# Esp32_Wroom_Contr_le_de_DELs.net
KiCad netlist of a schematic drawn in Altium Designer
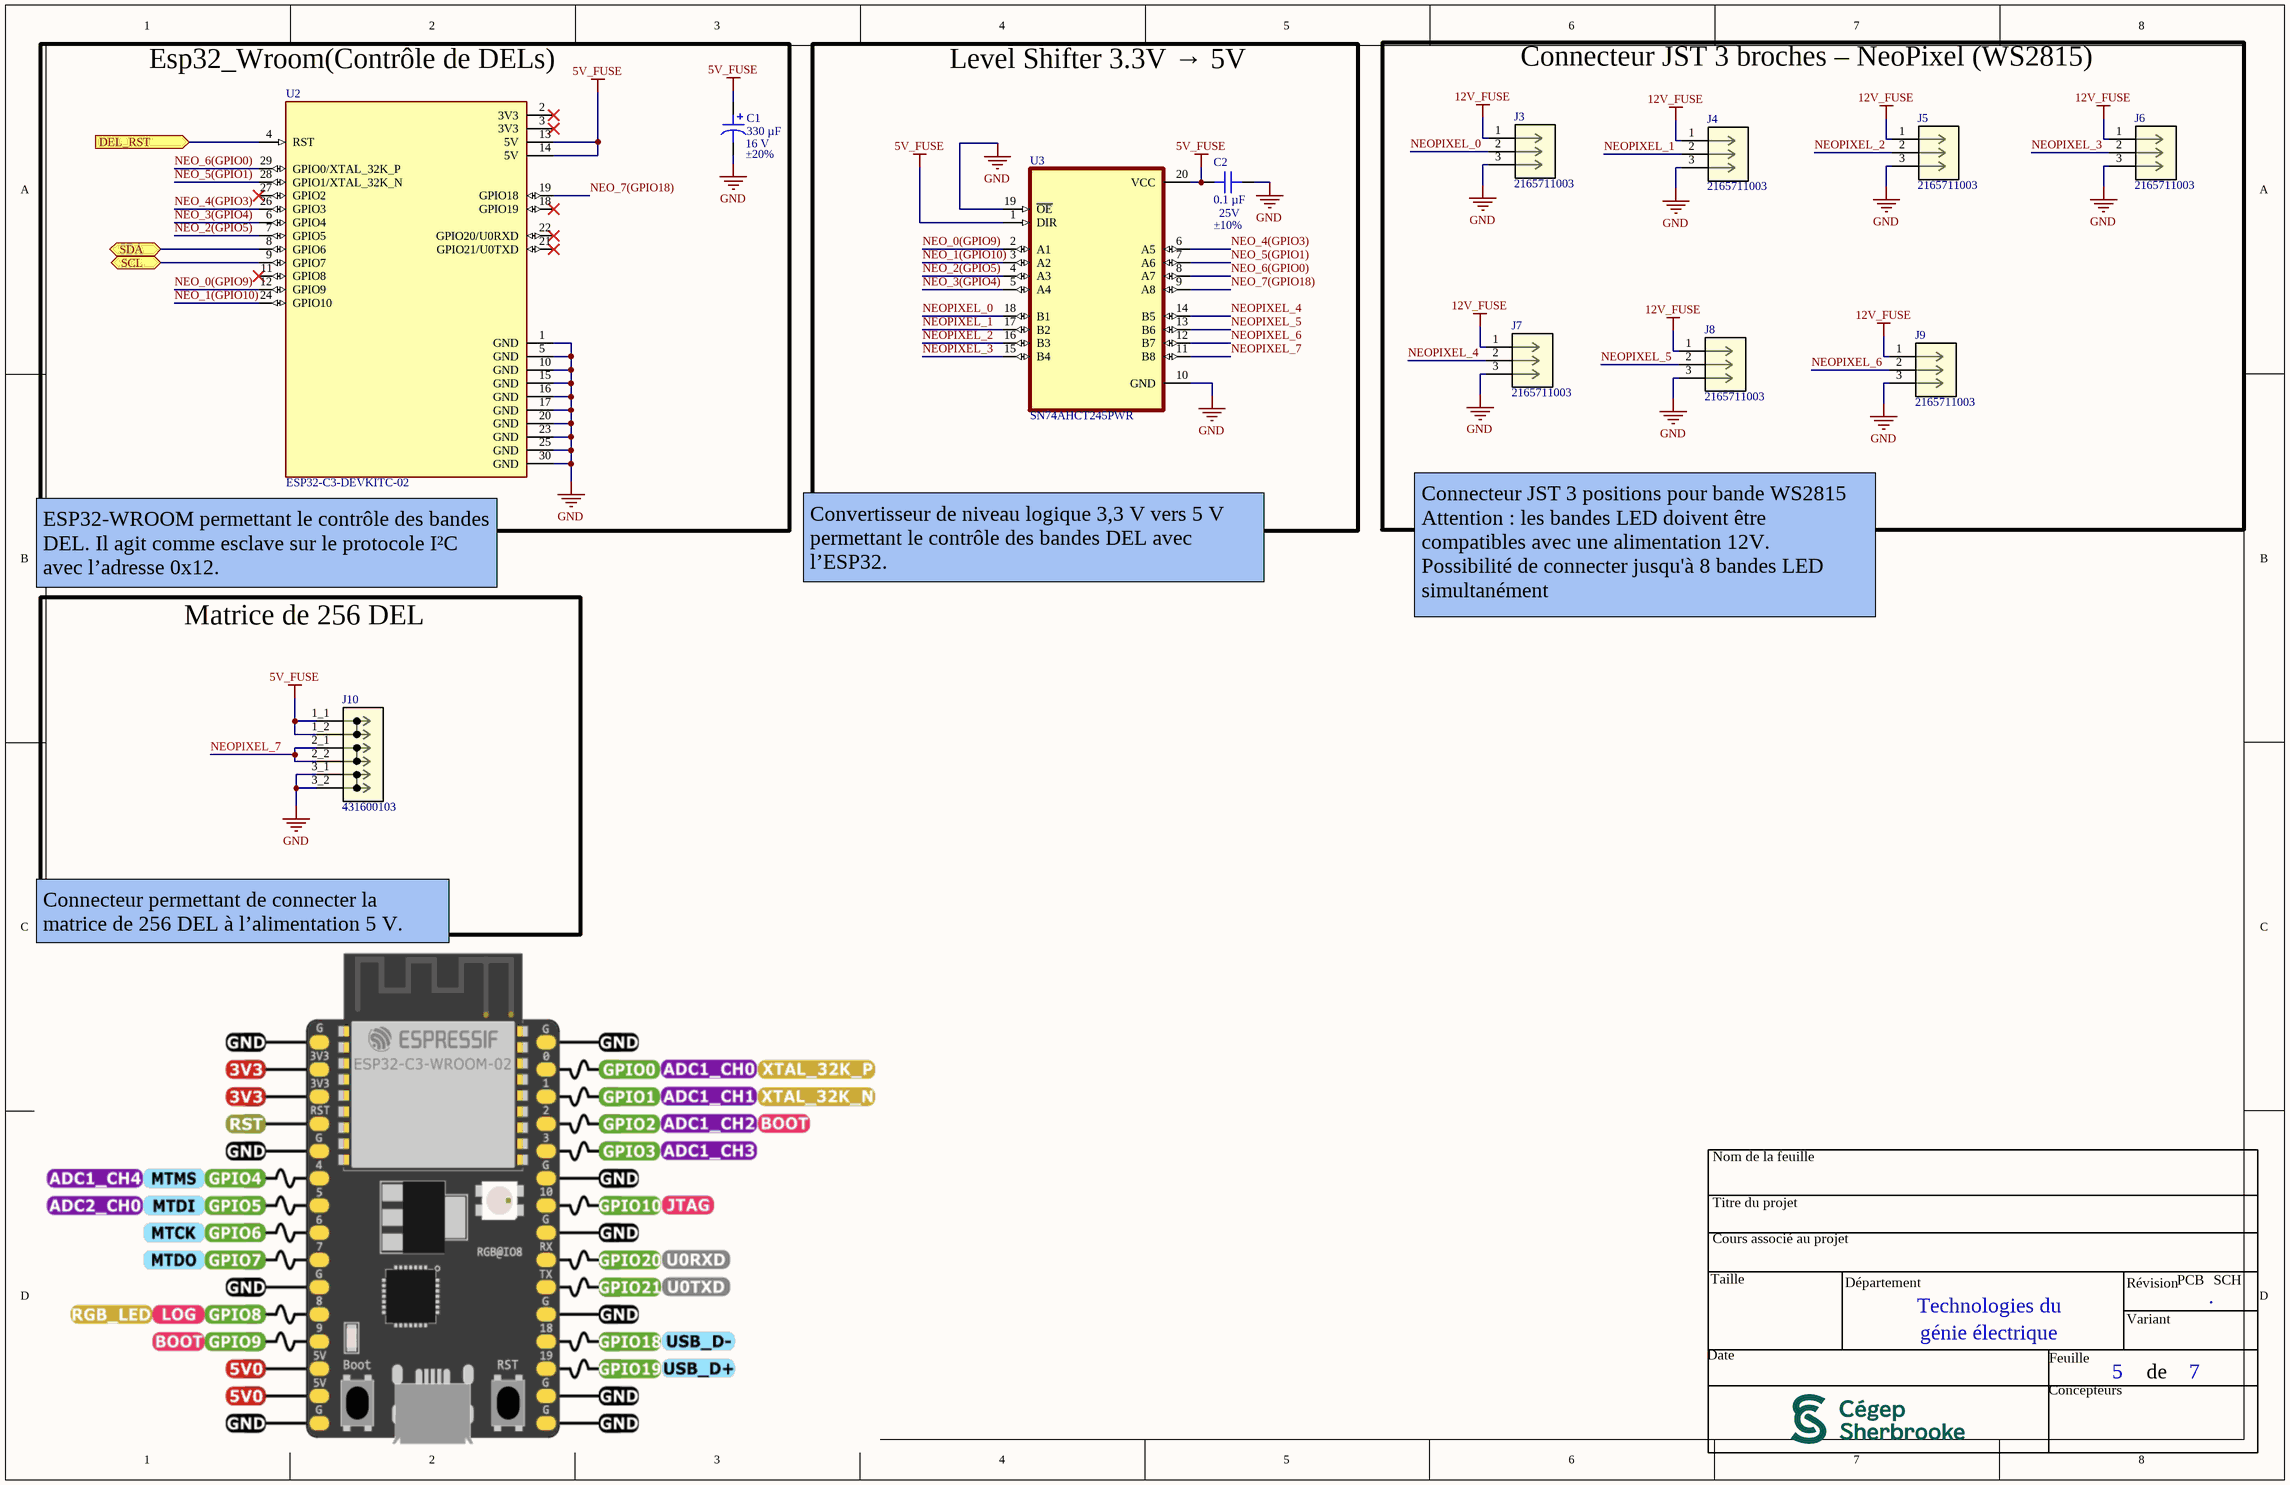
[diagram p0: Esp32_Wroom(Contrôle de DELs).SchDoc]

(export (version "E")
  (design (tool "Eeschema 10.0.6"))
  (components
    (comp (ref "C1")
      (value "330 µF")
      (footprint "CAP ALSMD 8.3MM H10.5MM")
      (description "CAP ALUM 330UF 20% 16V SMD")
      (fields
        (field (name "PART NUMBER") "865060353008")
        (field (name "MANUFACTURER") "Würth Elektronik")
        (field (name "TOLERANCE") "±20%")
        (field (name "VOLTAGE - RATED") "16 V")
      )
      (libsource (lib "Celestial Altium Library - altium_library") (part "Polarised Capacitor"))
    )
    (comp (ref "C2")
      (value "0.1 µF")
      (footprint "CAP 0805_2012")
      (description "CAP CER 0.1UF 25V X7R 0805")
      (fields
        (field (name "PART NUMBER") "0805Y0250104KXT")
        (field (name "CAPACITANCE") "0.1 µF")
        (field (name "MANUFACTURER") "Knowles Syfer")
        (field (name "TOLERANCE") "±10%")
        (field (name "VOLTAGE - RATED") "25V")
      )
      (libsource (lib "Celestial Altium Library - altium_library") (part "Capacitor"))
    )
    (comp (ref "J3")
      (value "2165711003")
      (footprint "CONN_2165710003-SD_03_MOL")
      (fields (field (name "COPYRIGHT") "Copyright (C) 2026 Ultra Librarian. All rights reserved."))
      (libsource (lib "2165711003") (part "2165711003"))
    )
    (comp (ref "J4")
      (value "2165711003")
      (footprint "CONN_2165710003-SD_03_MOL")
      (fields (field (name "COPYRIGHT") "Copyright (C) 2026 Ultra Librarian. All rights reserved."))
      (libsource (lib "2165711003") (part "2165711003"))
    )
    (comp (ref "J5")
      (value "2165711003")
      (footprint "CONN_2165710003-SD_03_MOL")
      (fields (field (name "COPYRIGHT") "Copyright (C) 2026 Ultra Librarian. All rights reserved."))
      (libsource (lib "2165711003") (part "2165711003"))
    )
    (comp (ref "J6")
      (value "2165711003")
      (footprint "CONN_2165710003-SD_03_MOL")
      (fields (field (name "COPYRIGHT") "Copyright (C) 2026 Ultra Librarian. All rights reserved."))
      (libsource (lib "2165711003") (part "2165711003"))
    )
    (comp (ref "J7")
      (value "2165711003")
      (footprint "CONN_2165710003-SD_03_MOL")
      (fields (field (name "COPYRIGHT") "Copyright (C) 2026 Ultra Librarian. All rights reserved."))
      (libsource (lib "2165711003") (part "2165711003"))
    )
    (comp (ref "J8")
      (value "2165711003")
      (footprint "CONN_2165710003-SD_03_MOL")
      (fields (field (name "COPYRIGHT") "Copyright (C) 2026 Ultra Librarian. All rights reserved."))
      (libsource (lib "2165711003") (part "2165711003"))
    )
    (comp (ref "J9")
      (value "2165711003")
      (footprint "CONN_2165710003-SD_03_MOL")
      (fields (field (name "COPYRIGHT") "Copyright (C) 2026 Ultra Librarian. All rights reserved."))
      (libsource (lib "2165711003") (part "2165711003"))
    )
    (comp (ref "J10")
      (value "431600103")
      (footprint "CONN_431600001-SD_V_03_MOL")
      (description "Sabre Vertical Header, 3 Circuits, Glow-Wire Capable, PCB Thickness 1.60mm, without Board Lock")
      (fields (field (name "COPYRIGHT") "Copyright (C) 2026 Ultra Librarian. All rights reserved."))
      (libsource (lib "431600103") (part "431600103"))
    )
    (comp (ref "U2")
      (value "ESP32-C3-DEVKITC-02")
      (footprint "XCVR_ESP32-C3-DEVKITC-02")
      (fields (field (name "MF") "Espressif Systems") (field (name "MP") "ESP32-C3-DevKitC-02"))
      (libsource (lib "ESP32-C3-DEVKITC-02") (part "ESP32-C3-DEVKITC-02"))
    )
    (comp (ref "U3")
      (value "SN74AHCT245PWR")
      (footprint "SOP65P640X120-20N")
      (libsource (lib "SN74AHCT245PWR") (part "SN74AHCT245PWR"))
    )
  )
  (nets
    (net (code "2") (name "/DEL_RST") (class "Default")
      (node (ref "U2") (pin "4") (pinfunction "RST_4") (pintype "input"))
    )
    (net (code "3") (name "/NEOPIXEL_0") (class "Default")
      (node (ref "J3") (pin "2") (pinfunction "2_2") (pintype "passive"))
      (node (ref "U3") (pin "18") (pinfunction "B1_18") (pintype "bidirectional"))
    )
    (net (code "4") (name "/NEOPIXEL_1") (class "Default")
      (node (ref "J4") (pin "2") (pinfunction "2_2") (pintype "passive"))
      (node (ref "U3") (pin "17") (pinfunction "B2_17") (pintype "bidirectional"))
    )
    (net (code "5") (name "/NEOPIXEL_2") (class "Default")
      (node (ref "J5") (pin "2") (pinfunction "2_2") (pintype "passive"))
      (node (ref "U3") (pin "16") (pinfunction "B3_16") (pintype "bidirectional"))
    )
    (net (code "6") (name "/NEOPIXEL_3") (class "Default")
      (node (ref "J6") (pin "2") (pinfunction "2_2") (pintype "passive"))
      (node (ref "U3") (pin "15") (pinfunction "B4_15") (pintype "bidirectional"))
    )
    (net (code "7") (name "/NEOPIXEL_4") (class "Default")
      (node (ref "J7") (pin "2") (pinfunction "2_2") (pintype "passive"))
      (node (ref "U3") (pin "14") (pinfunction "B5_14") (pintype "bidirectional"))
    )
    (net (code "8") (name "/NEOPIXEL_5") (class "Default")
      (node (ref "J8") (pin "2") (pinfunction "2_2") (pintype "passive"))
      (node (ref "U3") (pin "13") (pinfunction "B6_13") (pintype "bidirectional"))
    )
    (net (code "9") (name "/NEOPIXEL_6") (class "Default")
      (node (ref "J9") (pin "2") (pinfunction "2_2") (pintype "passive"))
      (node (ref "U3") (pin "12") (pinfunction "B7_12") (pintype "bidirectional"))
    )
    (net (code "10") (name "/NEOPIXEL_7") (class "Default")
      (node (ref "J10") (pin "2_1") (pinfunction "2_1_2_1") (pintype "passive"))
      (node (ref "J10") (pin "2_2") (pinfunction "2_2_2_2") (pintype "passive"))
      (node (ref "U3") (pin "11") (pinfunction "B8_11") (pintype "bidirectional"))
    )
    (net (code "11") (name "/NEO_0(GPIO9)") (class "Default")
      (node (ref "U2") (pin "12") (pinfunction "GPIO9_12") (pintype "bidirectional"))
      (node (ref "U3") (pin "2") (pinfunction "A1_2") (pintype "bidirectional"))
    )
    (net (code "12") (name "/NEO_1(GPIO10)") (class "Default")
      (node (ref "U2") (pin "24") (pinfunction "GPIO10_24") (pintype "bidirectional"))
      (node (ref "U3") (pin "3") (pinfunction "A2_3") (pintype "bidirectional"))
    )
    (net (code "13") (name "/NEO_2(GPIO5)") (class "Default")
      (node (ref "U2") (pin "7") (pinfunction "GPIO5_7") (pintype "bidirectional"))
      (node (ref "U3") (pin "4") (pinfunction "A3_4") (pintype "bidirectional"))
    )
    (net (code "14") (name "/NEO_3(GPIO4)") (class "Default")
      (node (ref "U2") (pin "6") (pinfunction "GPIO4_6") (pintype "bidirectional"))
      (node (ref "U3") (pin "5") (pinfunction "A4_5") (pintype "bidirectional"))
    )
    (net (code "15") (name "/NEO_4(GPIO3)") (class "Default")
      (node (ref "U2") (pin "26") (pinfunction "GPIO3_26") (pintype "bidirectional"))
      (node (ref "U3") (pin "6") (pinfunction "A5_6") (pintype "bidirectional"))
    )
    (net (code "16") (name "/NEO_5(GPIO1)") (class "Default")
      (node (ref "U2") (pin "28") (pinfunction "GPIO1/XTAL_32K_N_28") (pintype "bidirectional"))
      (node (ref "U3") (pin "7") (pinfunction "A6_7") (pintype "bidirectional"))
    )
    (net (code "17") (name "/NEO_6(GPIO0)") (class "Default")
      (node (ref "U2") (pin "29") (pinfunction "GPIO0/XTAL_32K_P_29") (pintype "bidirectional"))
      (node (ref "U3") (pin "8") (pinfunction "A7_8") (pintype "bidirectional"))
    )
    (net (code "18") (name "/NEO_7(GPIO18)") (class "Default")
      (node (ref "U2") (pin "19") (pinfunction "GPIO18_19") (pintype "bidirectional"))
      (node (ref "U3") (pin "9") (pinfunction "A8_9") (pintype "bidirectional"))
    )
    (net (code "19") (name "/SCL") (class "Default")
      (node (ref "U2") (pin "9") (pinfunction "GPIO7_9") (pintype "bidirectional"))
    )
    (net (code "20") (name "/SDA") (class "Default")
      (node (ref "U2") (pin "8") (pinfunction "GPIO6_8") (pintype "bidirectional"))
    )
    (net (code "21") (name "5V_FUSE") (class "Default")
      (node (ref "C1") (pin "1") (pinfunction "1_1") (pintype "passive"))
      (node (ref "C2") (pin "2") (pinfunction "2_2") (pintype "passive"))
      (node (ref "J10") (pin "1_1") (pinfunction "1_1_1_1") (pintype "passive"))
      (node (ref "J10") (pin "1_2") (pinfunction "1_2_1_2") (pintype "passive"))
      (node (ref "U2") (pin "13") (pinfunction "5V_13") (pintype "power_in"))
      (node (ref "U2") (pin "14") (pinfunction "5V_14") (pintype "power_in"))
      (node (ref "U3") (pin "1") (pinfunction "DIR_1") (pintype "input"))
      (node (ref "U3") (pin "20") (pinfunction "VCC_20") (pintype "power_in"))
    )
    (net (code "22") (name "12V_FUSE") (class "Default")
      (node (ref "J3") (pin "1") (pinfunction "1_1") (pintype "passive"))
      (node (ref "J4") (pin "1") (pinfunction "1_1") (pintype "passive"))
      (node (ref "J5") (pin "1") (pinfunction "1_1") (pintype "passive"))
      (node (ref "J6") (pin "1") (pinfunction "1_1") (pintype "passive"))
      (node (ref "J7") (pin "1") (pinfunction "1_1") (pintype "passive"))
      (node (ref "J8") (pin "1") (pinfunction "1_1") (pintype "passive"))
      (node (ref "J9") (pin "1") (pinfunction "1_1") (pintype "passive"))
    )
    (net (code "23") (name "GND") (class "Default")
      (node (ref "C1") (pin "2") (pinfunction "2_2") (pintype "passive"))
      (node (ref "C2") (pin "1") (pinfunction "1_1") (pintype "passive"))
      (node (ref "J10") (pin "3_1") (pinfunction "3_1_3_1") (pintype "passive"))
      (node (ref "J10") (pin "3_2") (pinfunction "3_2_3_2") (pintype "passive"))
      (node (ref "J3") (pin "3") (pinfunction "3_3") (pintype "passive"))
      (node (ref "J4") (pin "3") (pinfunction "3_3") (pintype "passive"))
      (node (ref "J5") (pin "3") (pinfunction "3_3") (pintype "passive"))
      (node (ref "J6") (pin "3") (pinfunction "3_3") (pintype "passive"))
      (node (ref "J7") (pin "3") (pinfunction "3_3") (pintype "passive"))
      (node (ref "J8") (pin "3") (pinfunction "3_3") (pintype "passive"))
      (node (ref "J9") (pin "3") (pinfunction "3_3") (pintype "passive"))
      (node (ref "U2") (pin "1") (pinfunction "GND_1") (pintype "power_in"))
      (node (ref "U2") (pin "10") (pinfunction "GND_10") (pintype "power_in"))
      (node (ref "U2") (pin "15") (pinfunction "GND_15") (pintype "power_in"))
      (node (ref "U2") (pin "16") (pinfunction "GND_16") (pintype "power_in"))
      (node (ref "U2") (pin "17") (pinfunction "GND_17") (pintype "power_in"))
      (node (ref "U2") (pin "20") (pinfunction "GND_20") (pintype "power_in"))
      (node (ref "U2") (pin "23") (pinfunction "GND_23") (pintype "power_in"))
      (node (ref "U2") (pin "25") (pinfunction "GND_25") (pintype "power_in"))
      (node (ref "U2") (pin "30") (pinfunction "GND_30") (pintype "power_in"))
      (node (ref "U2") (pin "5") (pinfunction "GND_5") (pintype "power_in"))
      (node (ref "U3") (pin "10") (pinfunction "GND_10") (pintype "power_in"))
      (node (ref "U3") (pin "19") (pinfunction "~{OE}_19") (pintype "input"))
    )
    (net (code "24") (name "unconnected-(U2-3V3-Pad2)") (class "Default")
      (node (ref "U2") (pin "2") (pinfunction "3V3_2") (pintype "power_in+no_connect"))
    )
    (net (code "25") (name "unconnected-(U2-3V3-Pad3)") (class "Default")
      (node (ref "U2") (pin "3") (pinfunction "3V3_3") (pintype "power_in+no_connect"))
    )
    (net (code "26") (name "unconnected-(U2-GPIO2-Pad27)") (class "Default")
      (node (ref "U2") (pin "27") (pinfunction "GPIO2_27") (pintype "bidirectional+no_connect"))
    )
    (net (code "27") (name "unconnected-(U2-GPIO8-Pad11)") (class "Default")
      (node (ref "U2") (pin "11") (pinfunction "GPIO8_11") (pintype "bidirectional+no_connect"))
    )
    (net (code "28") (name "unconnected-(U2-GPIO19-Pad18)") (class "Default")
      (node (ref "U2") (pin "18") (pinfunction "GPIO19_18") (pintype "bidirectional+no_connect"))
    )
    (net (code "29") (name "unconnected-(U2-GPIO20{slash}U0RXD-Pad22)") (class "Default")
      (node (ref "U2") (pin "22") (pinfunction "GPIO20/U0RXD_22") (pintype "bidirectional+no_connect"))
    )
    (net (code "30") (name "unconnected-(U2-GPIO21{slash}U0TXD-Pad21)") (class "Default")
      (node (ref "U2") (pin "21") (pinfunction "GPIO21/U0TXD_21") (pintype "bidirectional+no_connect"))
    )
  )
)
